# dsn-hat.net
KiCad netlist of a schematic drawn in EAGLE
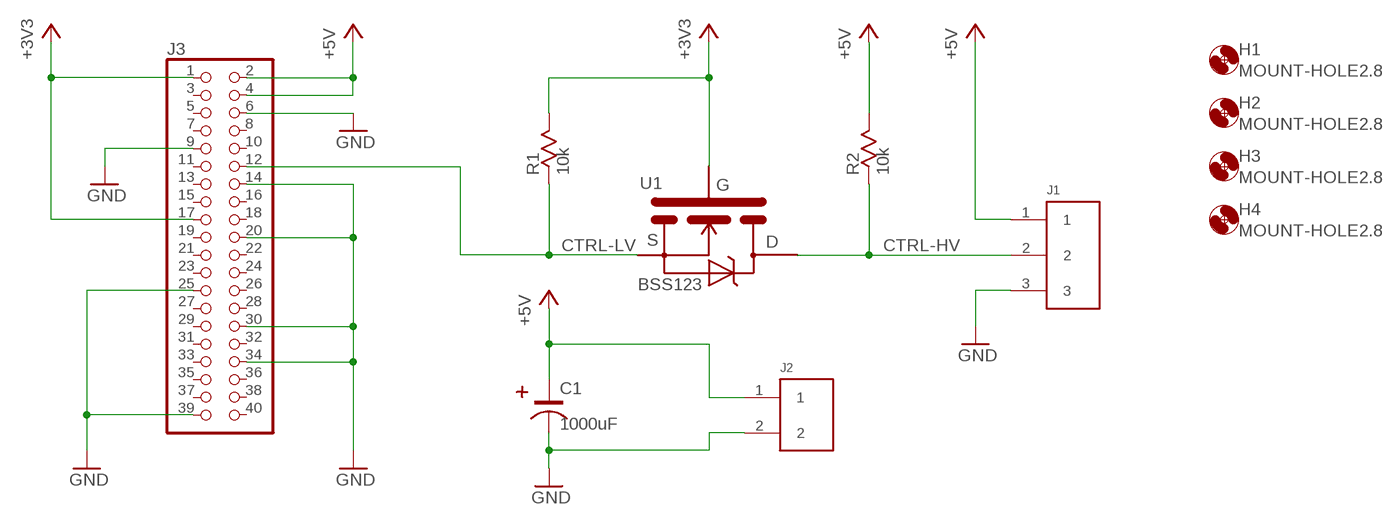
[diagram p0: schematic, sheet 1]

(export (version "E")
  (design (tool "Eeschema 10.0.6"))
  (components
    (comp (ref "C1")
      (value "1000uF")
      (footprint "eagle-import:CAP-TH")
      (libsource (lib "eagle-import") (part "CAP-E-THCAP-TH"))
    )
    (comp (ref "H1")
      (value "MOUNT-HOLE2.8")
      (footprint "eagle-import:2,8")
      (libsource (lib "eagle-import") (part "MOUNT-HOLE2.8"))
    )
    (comp (ref "H2")
      (value "MOUNT-HOLE2.8")
      (footprint "eagle-import:2,8")
      (libsource (lib "eagle-import") (part "MOUNT-HOLE2.8"))
    )
    (comp (ref "H3")
      (value "MOUNT-HOLE2.8")
      (footprint "eagle-import:2,8")
      (libsource (lib "eagle-import") (part "MOUNT-HOLE2.8"))
    )
    (comp (ref "H4")
      (value "MOUNT-HOLE2.8")
      (footprint "eagle-import:2,8")
      (libsource (lib "eagle-import") (part "MOUNT-HOLE2.8"))
    )
    (comp (ref "J1")
      (value "TERM-TH-3TERM-TH-3")
      (footprint "eagle-import:TERM-TH-3")
      (libsource (lib "eagle-import") (part "TERM-TH-3TERM-TH-3"))
    )
    (comp (ref "J2")
      (value "TERM-TH-2TH2")
      (footprint "eagle-import:TERM-TH-2")
      (libsource (lib "eagle-import") (part "TERM-TH-2TH2"))
    )
    (comp (ref "J3")
      (value "PINHD-2X20")
      (footprint "eagle-import:2X20")
      (libsource (lib "eagle-import") (part "PINHD-2X20"))
    )
    (comp (ref "R1")
      (value "10k")
      (footprint "eagle-import:R0805")
      (libsource (lib "eagle-import") (part "R08050805"))
    )
    (comp (ref "R2")
      (value "10k")
      (footprint "eagle-import:R0805")
      (libsource (lib "eagle-import") (part "R08050805"))
    )
    (comp (ref "U1")
      (value "BSS123")
      (footprint "eagle-import:SOT23")
      (libsource (lib "eagle-import") (part "BSS123BSS123-SOT23"))
    )
  )
  (nets
    (net (code "1") (name "+3V3") (class "Default")
      (node (ref "J3") (pin "1") (pinfunction "1_1") (pintype "passive"))
      (node (ref "J3") (pin "17") (pinfunction "17_17") (pintype "passive"))
      (node (ref "R1") (pin "1") (pinfunction "1_1") (pintype "passive"))
      (node (ref "U1") (pin "1") (pinfunction "G_1") (pintype "bidirectional"))
    )
    (net (code "2") (name "+5V") (class "Default")
      (node (ref "C1") (pin "POS") (pinfunction "POS_POS") (pintype "passive"))
      (node (ref "J1") (pin "1") (pinfunction "1_1") (pintype "bidirectional"))
      (node (ref "J2") (pin "1") (pinfunction "1_1") (pintype "bidirectional"))
      (node (ref "J3") (pin "2") (pinfunction "2_2") (pintype "passive"))
      (node (ref "J3") (pin "4") (pinfunction "4_4") (pintype "passive"))
      (node (ref "R2") (pin "1") (pinfunction "1_1") (pintype "passive"))
    )
    (net (code "3") (name "/CTRL-HV") (class "Default")
      (node (ref "J1") (pin "2") (pinfunction "2_2") (pintype "bidirectional"))
      (node (ref "R2") (pin "2") (pinfunction "2_2") (pintype "passive"))
      (node (ref "U1") (pin "3") (pinfunction "D_3") (pintype "bidirectional"))
    )
    (net (code "4") (name "/CTRL-LV") (class "Default")
      (node (ref "J3") (pin "12") (pinfunction "12_12") (pintype "passive"))
      (node (ref "R1") (pin "2") (pinfunction "2_2") (pintype "passive"))
      (node (ref "U1") (pin "2") (pinfunction "S_2") (pintype "bidirectional"))
    )
    (net (code "5") (name "GND") (class "Default")
      (node (ref "C1") (pin "NEG") (pinfunction "NEG_NEG") (pintype "passive"))
      (node (ref "J1") (pin "3") (pinfunction "3_3") (pintype "bidirectional"))
      (node (ref "J2") (pin "2") (pinfunction "2_2") (pintype "bidirectional"))
      (node (ref "J3") (pin "14") (pinfunction "14_14") (pintype "passive"))
      (node (ref "J3") (pin "20") (pinfunction "20_20") (pintype "passive"))
      (node (ref "J3") (pin "25") (pinfunction "25_25") (pintype "passive"))
      (node (ref "J3") (pin "30") (pinfunction "30_30") (pintype "passive"))
      (node (ref "J3") (pin "34") (pinfunction "34_34") (pintype "passive"))
      (node (ref "J3") (pin "39") (pinfunction "39_39") (pintype "passive"))
      (node (ref "J3") (pin "6") (pinfunction "6_6") (pintype "passive"))
      (node (ref "J3") (pin "9") (pinfunction "9_9") (pintype "passive"))
    )
    (net (code "6") (name "unconnected-(J3-Pad3)") (class "Default")
      (node (ref "J3") (pin "3") (pinfunction "3_3") (pintype "passive"))
    )
    (net (code "7") (name "unconnected-(J3-Pad5)") (class "Default")
      (node (ref "J3") (pin "5") (pinfunction "5_5") (pintype "passive"))
    )
    (net (code "8") (name "unconnected-(J3-Pad7)") (class "Default")
      (node (ref "J3") (pin "7") (pinfunction "7_7") (pintype "passive"))
    )
    (net (code "9") (name "unconnected-(J3-Pad8)") (class "Default")
      (node (ref "J3") (pin "8") (pinfunction "8_8") (pintype "passive"))
    )
    (net (code "10") (name "unconnected-(J3-Pad10)") (class "Default")
      (node (ref "J3") (pin "10") (pinfunction "10_10") (pintype "passive"))
    )
    (net (code "11") (name "unconnected-(J3-Pad11)") (class "Default")
      (node (ref "J3") (pin "11") (pinfunction "11_11") (pintype "passive"))
    )
    (net (code "12") (name "unconnected-(J3-Pad13)") (class "Default")
      (node (ref "J3") (pin "13") (pinfunction "13_13") (pintype "passive"))
    )
    (net (code "13") (name "unconnected-(J3-Pad15)") (class "Default")
      (node (ref "J3") (pin "15") (pinfunction "15_15") (pintype "passive"))
    )
    (net (code "14") (name "unconnected-(J3-Pad16)") (class "Default")
      (node (ref "J3") (pin "16") (pinfunction "16_16") (pintype "passive"))
    )
    (net (code "15") (name "unconnected-(J3-Pad18)") (class "Default")
      (node (ref "J3") (pin "18") (pinfunction "18_18") (pintype "passive"))
    )
    (net (code "16") (name "unconnected-(J3-Pad19)") (class "Default")
      (node (ref "J3") (pin "19") (pinfunction "19_19") (pintype "passive"))
    )
    (net (code "17") (name "unconnected-(J3-Pad21)") (class "Default")
      (node (ref "J3") (pin "21") (pinfunction "21_21") (pintype "passive"))
    )
    (net (code "18") (name "unconnected-(J3-Pad22)") (class "Default")
      (node (ref "J3") (pin "22") (pinfunction "22_22") (pintype "passive"))
    )
    (net (code "19") (name "unconnected-(J3-Pad23)") (class "Default")
      (node (ref "J3") (pin "23") (pinfunction "23_23") (pintype "passive"))
    )
    (net (code "20") (name "unconnected-(J3-Pad24)") (class "Default")
      (node (ref "J3") (pin "24") (pinfunction "24_24") (pintype "passive"))
    )
    (net (code "21") (name "unconnected-(J3-Pad26)") (class "Default")
      (node (ref "J3") (pin "26") (pinfunction "26_26") (pintype "passive"))
    )
    (net (code "22") (name "unconnected-(J3-Pad27)") (class "Default")
      (node (ref "J3") (pin "27") (pinfunction "27_27") (pintype "passive"))
    )
    (net (code "23") (name "unconnected-(J3-Pad28)") (class "Default")
      (node (ref "J3") (pin "28") (pinfunction "28_28") (pintype "passive"))
    )
    (net (code "24") (name "unconnected-(J3-Pad29)") (class "Default")
      (node (ref "J3") (pin "29") (pinfunction "29_29") (pintype "passive"))
    )
    (net (code "25") (name "unconnected-(J3-Pad31)") (class "Default")
      (node (ref "J3") (pin "31") (pinfunction "31_31") (pintype "passive"))
    )
    (net (code "26") (name "unconnected-(J3-Pad32)") (class "Default")
      (node (ref "J3") (pin "32") (pinfunction "32_32") (pintype "passive"))
    )
    (net (code "27") (name "unconnected-(J3-Pad33)") (class "Default")
      (node (ref "J3") (pin "33") (pinfunction "33_33") (pintype "passive"))
    )
    (net (code "28") (name "unconnected-(J3-Pad35)") (class "Default")
      (node (ref "J3") (pin "35") (pinfunction "35_35") (pintype "passive"))
    )
    (net (code "29") (name "unconnected-(J3-Pad36)") (class "Default")
      (node (ref "J3") (pin "36") (pinfunction "36_36") (pintype "passive"))
    )
    (net (code "30") (name "unconnected-(J3-Pad37)") (class "Default")
      (node (ref "J3") (pin "37") (pinfunction "37_37") (pintype "passive"))
    )
    (net (code "31") (name "unconnected-(J3-Pad38)") (class "Default")
      (node (ref "J3") (pin "38") (pinfunction "38_38") (pintype "passive"))
    )
    (net (code "32") (name "unconnected-(J3-Pad40)") (class "Default")
      (node (ref "J3") (pin "40") (pinfunction "40_40") (pintype "passive"))
    )
  )
)
